# H_Bridge_Rev0_2.net
KiCad netlist of a schematic drawn in Altium Designer
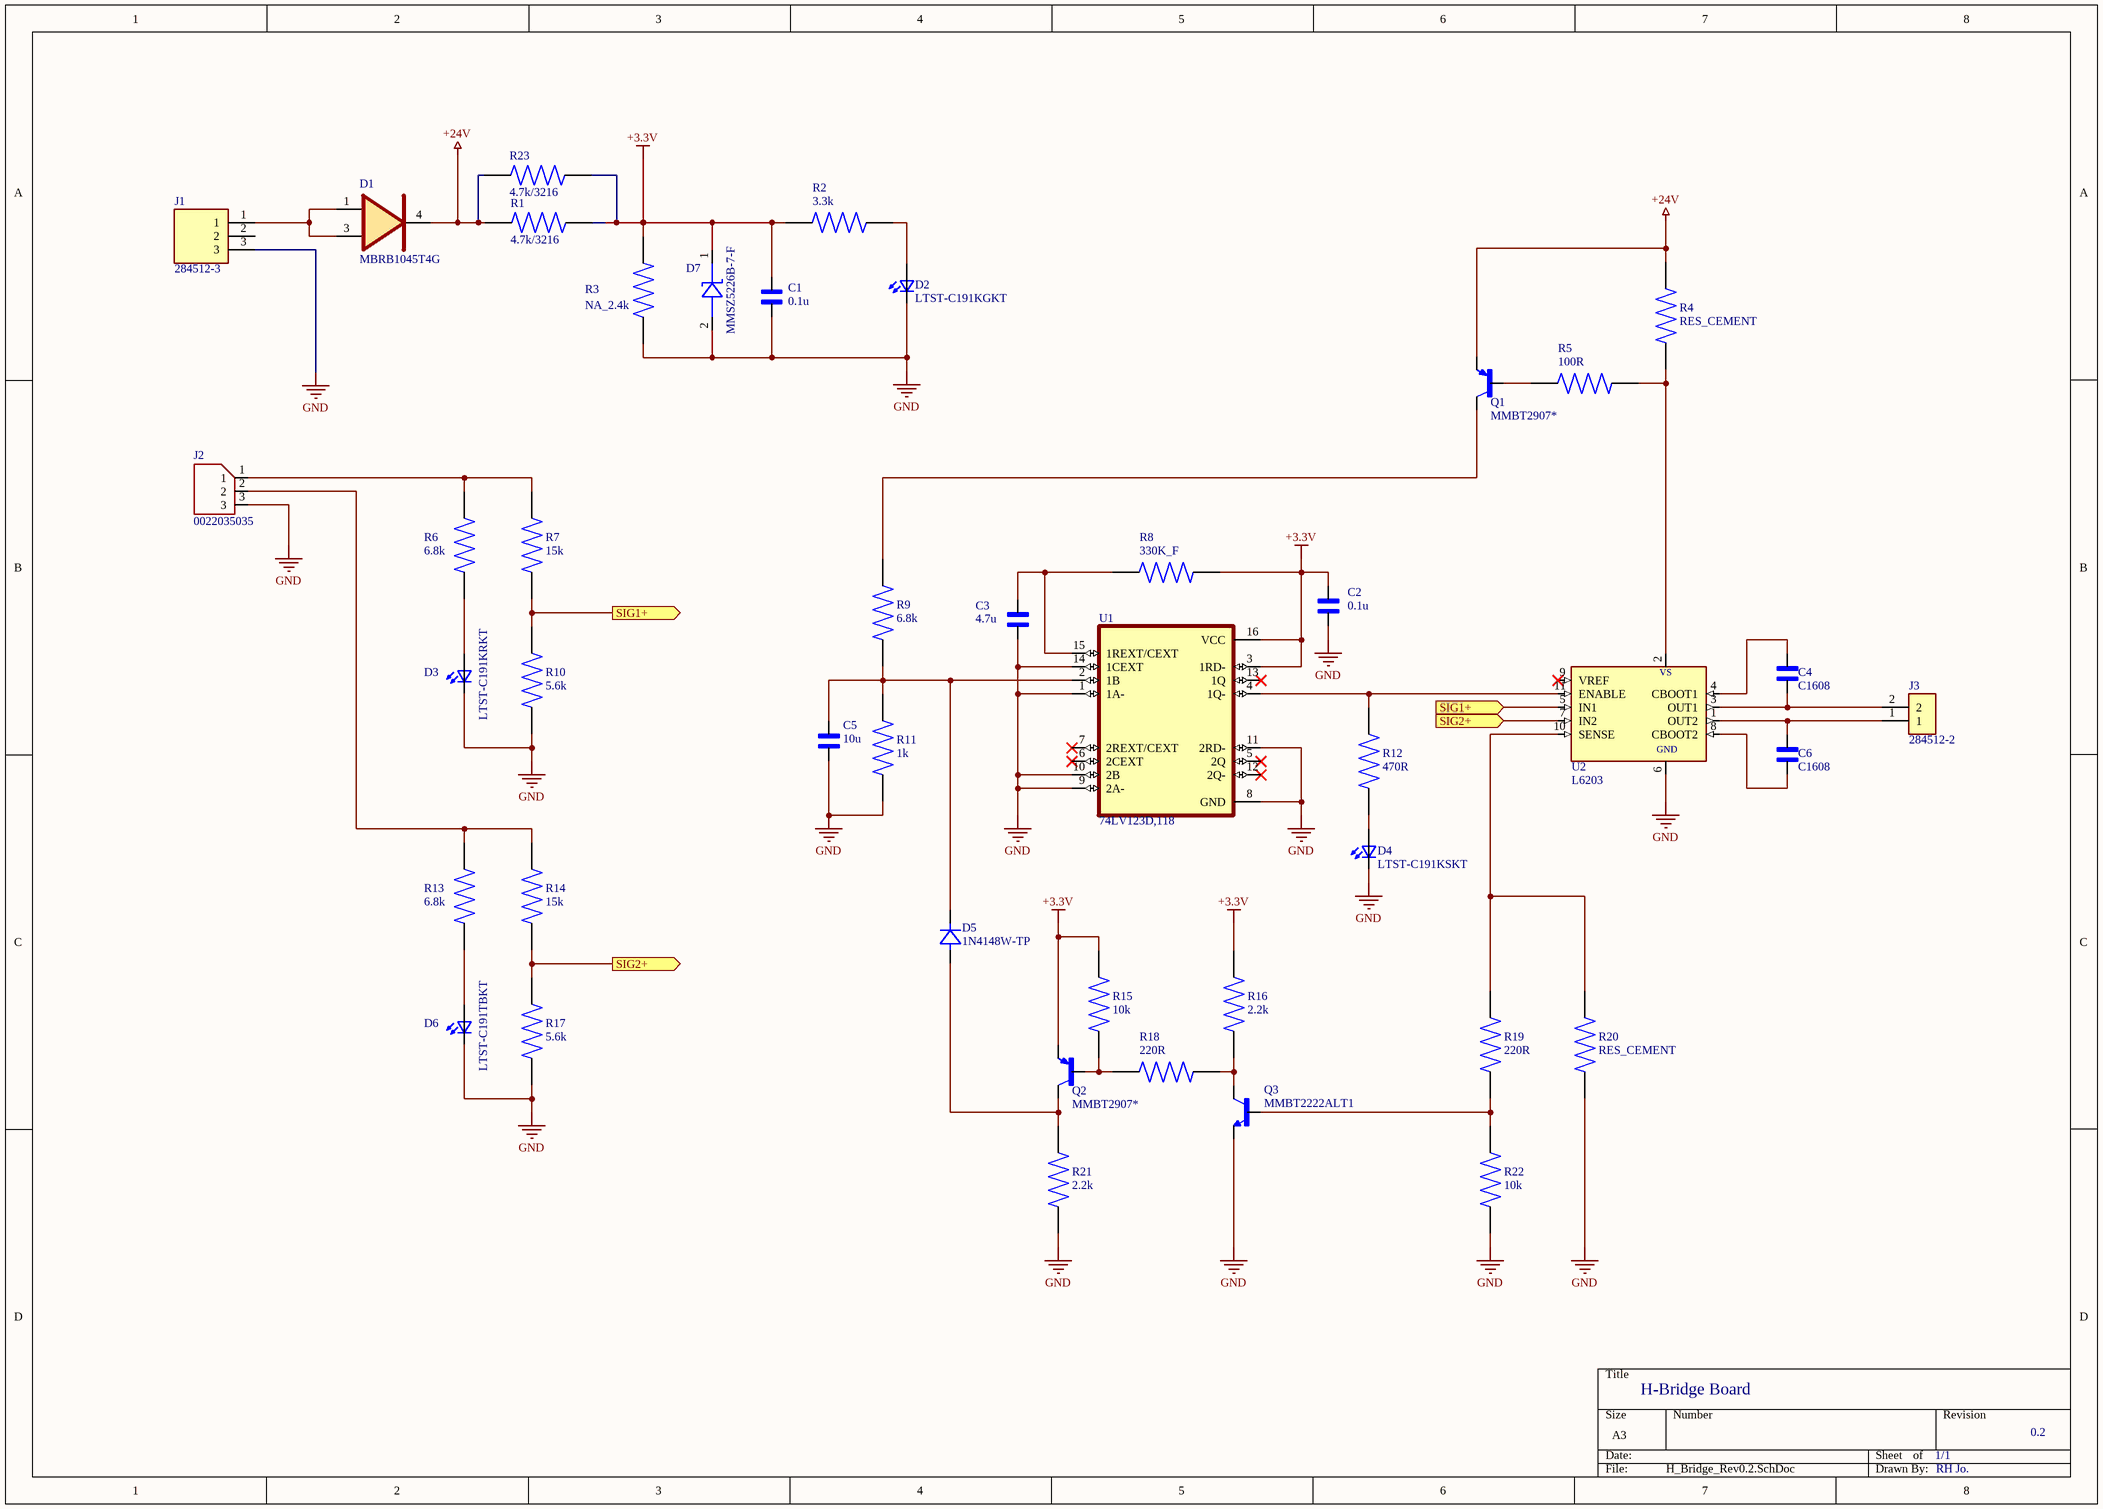
[diagram p0: H_Bridge_Rev0.2.SchDoc]

(export (version "E")
  (design (tool "Eeschema 10.0.6"))
  (components
    (comp (ref "C1")
      (value "0.1u")
      (footprint "C1608:C1608")
      (description "CAP1608")
      (libsource (lib "C1608") (part "C1608"))
    )
    (comp (ref "C2")
      (value "0.1u")
      (footprint "C1608:C1608")
      (description "CAP1608")
      (libsource (lib "C1608") (part "C1608"))
    )
    (comp (ref "C3")
      (value "4.7u")
      (footprint "C1608:C1608")
      (description "CAP1608")
      (libsource (lib "C1608") (part "C1608"))
    )
    (comp (ref "C4")
      (value "C1608")
      (footprint "C1608:C1608")
      (description "CAP1608")
      (libsource (lib "C1608") (part "C1608"))
    )
    (comp (ref "C5")
      (value "10u")
      (footprint "C1608:C1608")
      (description "CAP1608")
      (libsource (lib "C1608") (part "C1608"))
    )
    (comp (ref "C6")
      (value "C1608")
      (footprint "C1608:C1608")
      (description "CAP1608")
      (libsource (lib "C1608") (part "C1608"))
    )
    (comp (ref "D1")
      (value "MBRB1045T4G")
      (footprint "TO254P1524X483-3:TO254P1524X483-3")
      (description "Diode Schottky 45 V 10A Surface Mount DÂ²PAK")
      (fields (field (name "MF") "ON Semiconductor"))
      (libsource (lib "MBRB1045T4G") (part "MBRB1045T4G"))
    )
    (comp (ref "D2")
      (value "LTST-C191KGKT")
      (footprint "SnapEDApcb:0603")
      (description "Red 631nm LED Indication - Discrete 2V 0603 _1608 Metric_")
      (fields (field (name "MF") "Lite-On Inc.") (field (name "DIGI-KEY_PART_NUMBER") "160-1447-1-ND"))
      (libsource (lib "SnapEDAsch") (part "LTST-C191KRKT"))
    )
    (comp (ref "D3")
      (value "LTST-C191KRKT")
      (footprint "SnapEDApcb:0603")
      (description "Red 631nm LED Indication - Discrete 2V 0603 _1608 Metric_")
      (fields (field (name "MF") "Lite-On Inc.") (field (name "DIGI-KEY_PART_NUMBER") "160-1447-1-ND"))
      (libsource (lib "SnapEDAsch") (part "LTST-C191KRKT"))
    )
    (comp (ref "D4")
      (value "LTST-C191KSKT")
      (footprint "SnapEDApcb:0603")
      (description "Red 631nm LED Indication - Discrete 2V 0603 _1608 Metric_")
      (fields (field (name "MF") "Lite-On Inc.") (field (name "DIGI-KEY_PART_NUMBER") "160-1447-1-ND"))
      (libsource (lib "SnapEDAsch") (part "LTST-C191KRKT"))
    )
    (comp (ref "D5")
      (value "1N4148W-TP")
      (footprint "SnapEDApcb:SOD123")
      (description "Diode Standard 100V 150mA Surface Mount SOD-123")
      (fields (field (name "MF") "Micro Commercial"))
      (libsource (lib "SnapEDAsch") (part "1N4148W-TP"))
    )
    (comp (ref "D6")
      (value "LTST-C191TBKT")
      (footprint "SnapEDApcb:0603")
      (description "Red 631nm LED Indication - Discrete 2V 0603 _1608 Metric_")
      (fields (field (name "MF") "Lite-On Inc.") (field (name "DIGI-KEY_PART_NUMBER") "160-1447-1-ND"))
      (libsource (lib "SnapEDAsch") (part "LTST-C191KRKT"))
    )
    (comp (ref "D7")
      (value "MMSZ5226B-7-F")
      (footprint "SnapEDApcb:SOD3715X135L32X57N")
      (description "Zener Diode 3.3V 500mW Â±5% Surface Mount SOD-123")
      (fields (field (name "MF") "Diodes Inc."))
      (libsource (lib "SnapEDAsch") (part "MMSZ5226B-7-F"))
    )
    (comp (ref "J1")
      (value "284512-3")
      (footprint "SnapEDApcb:TE_284512-3")
      (description "Pluggable terminal block; socket; male; angled; 3.5mm;")
      (fields (field (name "MF") "TE Connectivity"))
      (libsource (lib "SnapEDAsch") (part "284512-3"))
    )
    (comp (ref "J2")
      (value "0022035035")
      (footprint "0022035035:MOLEX22035035")
      (description "Connector Header Through Hole 4 position 0.098 _2.50mm_")
      (fields (field (name "MP") "0022035045") (field (name "MF") "Molex, LLC"))
      (libsource (lib "0022035035") (part "0022035045"))
    )
    (comp (ref "J3")
      (value "284512-2")
      (footprint "SnapEDApcb:TE_284512-2")
      (description "Terminal Block Header, 2, 300 V, 11 A, 3.5 mm, Through Hole Right Angle, Header")
      (fields (field (name "MF") "TE Connectivity"))
      (libsource (lib "SnapEDAsch") (part "284512-2"))
    )
    (comp (ref "Q1")
      (value "MMBT2907*")
      (footprint "SnapEDApcb:SOT23-BEC")
      (description "Bipolar _BJT_ Transistor PNP 60V 600mA 200MHz 300mW Surface Mount SOT-23-3")
      (fields
        (field (name "DIGI-KEY_PART_NUMBER") "MMBT2907A-FDICT-ND")
        (field (name "MF") "ON Semiconductor")
      )
      (libsource (lib "SnapEDAsch") (part "MMBT2907*"))
    )
    (comp (ref "Q2")
      (value "MMBT2907*")
      (footprint "SnapEDApcb:SOT23-BEC")
      (description "Bipolar _BJT_ Transistor PNP 60V 600mA 200MHz 300mW Surface Mount SOT-23-3")
      (fields
        (field (name "DIGI-KEY_PART_NUMBER") "MMBT2907A-FDICT-ND")
        (field (name "MF") "ON Semiconductor")
      )
      (libsource (lib "SnapEDAsch") (part "MMBT2907*"))
    )
    (comp (ref "Q3")
      (value "MMBT2222ALT1")
      (footprint "SOT95P237X111-3N:SOT95P237X111-3N")
      (description "Bipolar (BJT) Transistor NPN 40V 600mA 300MHz 225mW Surface Mount SOT-23")
      (fields (field (name "MF") "ON Semiconductor"))
      (libsource (lib "MMBT2222ALT1") (part "MMBT2222ALT1"))
    )
    (comp (ref "R1")
      (value "4.7k/3216")
      (footprint "R3216:R3216")
      (description "Res 3216")
      (fields (field (name "TOLERANCE") "5%") (field (name "MP") "FCR1206J10R"))
      (libsource (lib "R3216") (part "R3216"))
    )
    (comp (ref "R2")
      (value "3.3k")
      (footprint "R1608:R1608")
      (description "R1608")
      (libsource (lib "R1608") (part "R1608"))
    )
    (comp (ref "R3")
      (value "NA_2.4k")
      (footprint "R1608:R1608")
      (description "R1608")
      (libsource (lib "R1608") (part "R1608"))
    )
    (comp (ref "R4")
      (value "RES_CEMENT")
      (footprint "RES_CEMENT")
      (libsource (lib "RES_CEMENT") (part "RES_CEMENT"))
    )
    (comp (ref "R5")
      (value "100R")
      (footprint "R1608:R1608")
      (description "R1608")
      (libsource (lib "R1608") (part "R1608"))
    )
    (comp (ref "R6")
      (value "6.8k")
      (footprint "R1608:R1608")
      (description "R1608")
      (libsource (lib "R1608") (part "R1608"))
    )
    (comp (ref "R7")
      (value "15k")
      (footprint "R1608:R1608")
      (description "R1608")
      (libsource (lib "R1608") (part "R1608"))
    )
    (comp (ref "R8")
      (value "330K_F")
      (footprint "R1608:R1608")
      (description "R1608")
      (libsource (lib "R1608") (part "R1608"))
    )
    (comp (ref "R9")
      (value "6.8k")
      (footprint "R1608:R1608")
      (description "R1608")
      (libsource (lib "R1608") (part "R1608"))
    )
    (comp (ref "R10")
      (value "5.6k")
      (footprint "R1608:R1608")
      (description "R1608")
      (libsource (lib "R1608") (part "R1608"))
    )
    (comp (ref "R11")
      (value "1k")
      (footprint "R1608:R1608")
      (description "R1608")
      (libsource (lib "R1608") (part "R1608"))
    )
    (comp (ref "R12")
      (value "470R")
      (footprint "R1608:R1608")
      (description "R1608")
      (libsource (lib "R1608") (part "R1608"))
    )
    (comp (ref "R13")
      (value "6.8k")
      (footprint "R1608:R1608")
      (description "R1608")
      (libsource (lib "R1608") (part "R1608"))
    )
    (comp (ref "R14")
      (value "15k")
      (footprint "R1608:R1608")
      (description "R1608")
      (libsource (lib "R1608") (part "R1608"))
    )
    (comp (ref "R15")
      (value "10k")
      (footprint "R1608:R1608")
      (description "R1608")
      (libsource (lib "R1608") (part "R1608"))
    )
    (comp (ref "R16")
      (value "2.2k")
      (footprint "R1608:R1608")
      (description "R1608")
      (libsource (lib "R1608") (part "R1608"))
    )
    (comp (ref "R17")
      (value "5.6k")
      (footprint "R1608:R1608")
      (description "R1608")
      (libsource (lib "R1608") (part "R1608"))
    )
    (comp (ref "R18")
      (value "220R")
      (footprint "R1608:R1608")
      (description "R1608")
      (libsource (lib "R1608") (part "R1608"))
    )
    (comp (ref "R19")
      (value "220R")
      (footprint "R1608:R1608")
      (description "R1608")
      (libsource (lib "R1608") (part "R1608"))
    )
    (comp (ref "R20")
      (value "RES_CEMENT")
      (footprint "RES_CEMENT")
      (libsource (lib "RES_CEMENT") (part "RES_CEMENT"))
    )
    (comp (ref "R21")
      (value "2.2k")
      (footprint "R1608:R1608")
      (description "R1608")
      (libsource (lib "R1608") (part "R1608"))
    )
    (comp (ref "R22")
      (value "10k")
      (footprint "R1608:R1608")
      (description "R1608")
      (libsource (lib "R1608") (part "R1608"))
    )
    (comp (ref "R23")
      (value "4.7k/3216")
      (footprint "R3216:R3216")
      (description "Res 3216")
      (fields (field (name "TOLERANCE") "5%") (field (name "MP") "FCR1206J10R"))
      (libsource (lib "R3216") (part "R3216"))
    )
    (comp (ref "U1")
      (value "74LV123D,118")
      (footprint "SOIC127P600X175-16N:SOIC127P600X175-16N")
      (description "Monostable Multivibrator Dual-Element -40Â°C 125Â°C Automotive 16-Pin SO T/R")
      (fields (field (name "MF") "Nexperia"))
      (libsource (lib "74LV123D,118") (part "74LV123D,118"))
    )
    (comp (ref "U2")
      (value "L6203")
      (footprint "SnapEDApcb:MULTIWATT-11")
      (description "Half Bridge _2_ Driver DC Motors, General Purpose BCDMOS 11-Multiwatt")
      (fields (field (name "MF") "STMicroelectronics"))
      (libsource (lib "SnapEDAsch") (part "L6203"))
    )
  )
  (nets
    (net (code "1") (name "+3.3V") (class "Default")
      (node (ref "C1") (pin "2") (pinfunction "2_2") (pintype "passive"))
      (node (ref "C2") (pin "2") (pinfunction "2_2") (pintype "passive"))
      (node (ref "D7") (pin "1") (pinfunction "C_1") (pintype "passive"))
      (node (ref "Q2") (pin "E") (pinfunction "E_E") (pintype "passive"))
      (node (ref "R1") (pin "2") (pinfunction "2_2") (pintype "passive"))
      (node (ref "R15") (pin "2") (pinfunction "2_2") (pintype "passive"))
      (node (ref "R16") (pin "2") (pinfunction "2_2") (pintype "passive"))
      (node (ref "R2") (pin "1") (pinfunction "1_1") (pintype "passive"))
      (node (ref "R23") (pin "2") (pinfunction "2_2") (pintype "passive"))
      (node (ref "R3") (pin "2") (pinfunction "2_2") (pintype "passive"))
      (node (ref "R8") (pin "2") (pinfunction "2_2") (pintype "passive"))
      (node (ref "U1") (pin "16") (pinfunction "VCC_16") (pintype "power_in"))
      (node (ref "U1") (pin "3") (pinfunction "1RD-_3") (pintype "bidirectional"))
    )
    (net (code "2") (name "+24V") (class "Default")
      (node (ref "D1") (pin "4") (pinfunction "OUT_4") (pintype "power_in"))
      (node (ref "Q1") (pin "E") (pinfunction "E_E") (pintype "passive"))
      (node (ref "R1") (pin "1") (pinfunction "1_1") (pintype "passive"))
      (node (ref "R23") (pin "1") (pinfunction "1_1") (pintype "passive"))
      (node (ref "R4") (pin "2") (pinfunction "2_2") (pintype "passive"))
    )
    (net (code "3") (name "/SIG1+") (class "Default")
      (node (ref "R10") (pin "2") (pinfunction "2_2") (pintype "passive"))
      (node (ref "R7") (pin "1") (pinfunction "1_1") (pintype "passive"))
      (node (ref "U2") (pin "5") (pinfunction "IN1_5") (pintype "input"))
    )
    (net (code "4") (name "/SIG2+") (class "Default")
      (node (ref "R14") (pin "1") (pinfunction "1_1") (pintype "passive"))
      (node (ref "R17") (pin "2") (pinfunction "2_2") (pintype "passive"))
      (node (ref "U2") (pin "7") (pinfunction "IN2_7") (pintype "input"))
    )
    (net (code "5") (name "GND") (class "Default")
      (node (ref "C1") (pin "1") (pinfunction "1_1") (pintype "passive"))
      (node (ref "C2") (pin "1") (pinfunction "1_1") (pintype "passive"))
      (node (ref "C3") (pin "1") (pinfunction "1_1") (pintype "passive"))
      (node (ref "C5") (pin "1") (pinfunction "1_1") (pintype "passive"))
      (node (ref "D2") (pin "1") (pinfunction "K2_1") (pintype "passive"))
      (node (ref "D3") (pin "1") (pinfunction "K2_1") (pintype "passive"))
      (node (ref "D4") (pin "1") (pinfunction "K2_1") (pintype "passive"))
      (node (ref "D6") (pin "1") (pinfunction "K2_1") (pintype "passive"))
      (node (ref "D7") (pin "2") (pinfunction "A_2") (pintype "passive"))
      (node (ref "J1") (pin "3") (pinfunction "3_3") (pintype "passive"))
      (node (ref "J2") (pin "3") (pinfunction "3_3") (pintype "passive"))
      (node (ref "Q3") (pin "2") (pinfunction "E_2") (pintype "passive"))
      (node (ref "R10") (pin "1") (pinfunction "1_1") (pintype "passive"))
      (node (ref "R11") (pin "1") (pinfunction "1_1") (pintype "passive"))
      (node (ref "R17") (pin "1") (pinfunction "1_1") (pintype "passive"))
      (node (ref "R20") (pin "1") (pinfunction "1_1") (pintype "passive"))
      (node (ref "R21") (pin "1") (pinfunction "1_1") (pintype "passive"))
      (node (ref "R22") (pin "1") (pinfunction "1_1") (pintype "passive"))
      (node (ref "R3") (pin "1") (pinfunction "1_1") (pintype "passive"))
      (node (ref "U1") (pin "1") (pinfunction "1A-_1") (pintype "bidirectional"))
      (node (ref "U1") (pin "10") (pinfunction "2B_10") (pintype "bidirectional"))
      (node (ref "U1") (pin "11") (pinfunction "2RD-_11") (pintype "bidirectional"))
      (node (ref "U1") (pin "14") (pinfunction "1CEXT_14") (pintype "bidirectional"))
      (node (ref "U1") (pin "8") (pinfunction "GND_8") (pintype "power_in"))
      (node (ref "U1") (pin "9") (pinfunction "2A-_9") (pintype "bidirectional"))
      (node (ref "U2") (pin "6") (pinfunction "GND_6") (pintype "power_in"))
    )
    (net (code "6") (name "Net-(D1-IN)") (class "Default")
      (node (ref "D1") (pin "1") (pinfunction "IN-1_1") (pintype "power_in"))
      (node (ref "D1") (pin "3") (pinfunction "IN_3") (pintype "power_in"))
      (node (ref "J1") (pin "1") (pinfunction "1_1") (pintype "passive"))
    )
    (net (code "7") (name "Net-(D2-A2)") (class "Default")
      (node (ref "D2") (pin "2") (pinfunction "A2_2") (pintype "passive"))
      (node (ref "R2") (pin "2") (pinfunction "2_2") (pintype "passive"))
    )
    (net (code "8") (name "Net-(D3-A2)") (class "Default")
      (node (ref "D3") (pin "2") (pinfunction "A2_2") (pintype "passive"))
      (node (ref "R6") (pin "1") (pinfunction "1_1") (pintype "passive"))
    )
    (net (code "9") (name "Net-(D4-A2)") (class "Default")
      (node (ref "D4") (pin "2") (pinfunction "A2_2") (pintype "passive"))
      (node (ref "R12") (pin "1") (pinfunction "1_1") (pintype "passive"))
    )
    (net (code "10") (name "Net-(D5-Pad2)") (class "Default")
      (node (ref "D5") (pin "2") (pinfunction "2_2") (pintype "passive"))
      (node (ref "Q2") (pin "C") (pinfunction "C_C") (pintype "passive"))
      (node (ref "R21") (pin "2") (pinfunction "2_2") (pintype "passive"))
    )
    (net (code "11") (name "Net-(D6-A2)") (class "Default")
      (node (ref "D6") (pin "2") (pinfunction "A2_2") (pintype "passive"))
      (node (ref "R13") (pin "1") (pinfunction "1_1") (pintype "passive"))
    )
    (net (code "12") (name "Net-(J2-Pad1)") (class "Default")
      (node (ref "J2") (pin "1") (pinfunction "1_1") (pintype "passive"))
      (node (ref "R6") (pin "2") (pinfunction "2_2") (pintype "passive"))
      (node (ref "R7") (pin "2") (pinfunction "2_2") (pintype "passive"))
    )
    (net (code "13") (name "Net-(J2-Pad2)") (class "Default")
      (node (ref "J2") (pin "2") (pinfunction "2_2") (pintype "passive"))
      (node (ref "R13") (pin "2") (pinfunction "2_2") (pintype "passive"))
      (node (ref "R14") (pin "2") (pinfunction "2_2") (pintype "passive"))
    )
    (net (code "14") (name "Net-(Q1-PadB)") (class "Default")
      (node (ref "Q1") (pin "B") (pinfunction "B_B") (pintype "passive"))
      (node (ref "R5") (pin "1") (pinfunction "1_1") (pintype "passive"))
    )
    (net (code "15") (name "Net-(Q1-PadC)") (class "Default")
      (node (ref "Q1") (pin "C") (pinfunction "C_C") (pintype "passive"))
      (node (ref "R9") (pin "2") (pinfunction "2_2") (pintype "passive"))
    )
    (net (code "16") (name "Net-(Q2-PadB)") (class "Default")
      (node (ref "Q2") (pin "B") (pinfunction "B_B") (pintype "passive"))
      (node (ref "R15") (pin "1") (pinfunction "1_1") (pintype "passive"))
      (node (ref "R18") (pin "1") (pinfunction "1_1") (pintype "passive"))
    )
    (net (code "17") (name "Net-(Q3-B)") (class "Default")
      (node (ref "Q3") (pin "1") (pinfunction "B_1") (pintype "passive"))
      (node (ref "R19") (pin "1") (pinfunction "1_1") (pintype "passive"))
      (node (ref "R22") (pin "2") (pinfunction "2_2") (pintype "passive"))
    )
    (net (code "18") (name "Net-(Q3-C)") (class "Default")
      (node (ref "Q3") (pin "3") (pinfunction "C_3") (pintype "passive"))
      (node (ref "R16") (pin "1") (pinfunction "1_1") (pintype "passive"))
      (node (ref "R18") (pin "2") (pinfunction "2_2") (pintype "passive"))
    )
    (net (code "19") (name "Net-(U1-1B)") (class "Default")
      (node (ref "C5") (pin "2") (pinfunction "2_2") (pintype "passive"))
      (node (ref "D5") (pin "1") (pinfunction "1_1") (pintype "passive"))
      (node (ref "R11") (pin "2") (pinfunction "2_2") (pintype "passive"))
      (node (ref "R9") (pin "1") (pinfunction "1_1") (pintype "passive"))
      (node (ref "U1") (pin "2") (pinfunction "1B_2") (pintype "bidirectional"))
    )
    (net (code "20") (name "Net-(U1-1Q-)") (class "Default")
      (node (ref "R12") (pin "2") (pinfunction "2_2") (pintype "passive"))
      (node (ref "U1") (pin "4") (pinfunction "1Q-_4") (pintype "bidirectional"))
      (node (ref "U2") (pin "11") (pinfunction "ENABLE_11") (pintype "input"))
    )
    (net (code "21") (name "Net-(U1-1REXT{slash}CEXT)") (class "Default")
      (node (ref "C3") (pin "2") (pinfunction "2_2") (pintype "passive"))
      (node (ref "R8") (pin "1") (pinfunction "1_1") (pintype "passive"))
      (node (ref "U1") (pin "15") (pinfunction "1REXT/CEXT_15") (pintype "bidirectional"))
    )
    (net (code "22") (name "Net-(U2-CBOOT1)") (class "Default")
      (node (ref "C4") (pin "2") (pinfunction "2_2") (pintype "passive"))
      (node (ref "U2") (pin "4") (pinfunction "CBOOT1_4") (pintype "input"))
    )
    (net (code "23") (name "Net-(U2-CBOOT2)") (class "Default")
      (node (ref "C6") (pin "1") (pinfunction "1_1") (pintype "passive"))
      (node (ref "U2") (pin "8") (pinfunction "CBOOT2_8") (pintype "input"))
    )
    (net (code "24") (name "Net-(U2-OUT1)") (class "Default")
      (node (ref "C4") (pin "1") (pinfunction "1_1") (pintype "passive"))
      (node (ref "J3") (pin "2") (pinfunction "2_2") (pintype "passive"))
      (node (ref "U2") (pin "3") (pinfunction "OUT1_3") (pintype "output"))
    )
    (net (code "25") (name "Net-(U2-OUT2)") (class "Default")
      (node (ref "C6") (pin "2") (pinfunction "2_2") (pintype "passive"))
      (node (ref "J3") (pin "1") (pinfunction "1_1") (pintype "passive"))
      (node (ref "U2") (pin "1") (pinfunction "OUT2_1") (pintype "output"))
    )
    (net (code "26") (name "Net-(U2-SENSE)") (class "Default")
      (node (ref "R19") (pin "2") (pinfunction "2_2") (pintype "passive"))
      (node (ref "R20") (pin "2") (pinfunction "2_2") (pintype "passive"))
      (node (ref "U2") (pin "10") (pinfunction "SENSE_10") (pintype "input"))
    )
    (net (code "27") (name "Net-(U2-VS)") (class "Default")
      (node (ref "R4") (pin "1") (pinfunction "1_1") (pintype "passive"))
      (node (ref "R5") (pin "2") (pinfunction "2_2") (pintype "passive"))
      (node (ref "U2") (pin "2") (pinfunction "VS_2") (pintype "power_in"))
    )
    (net (code "28") (name "unconnected-(J1-Pad2)") (class "Default")
      (node (ref "J1") (pin "2") (pinfunction "2_2") (pintype "passive"))
    )
    (net (code "29") (name "unconnected-(U1-1Q-Pad13)") (class "Default")
      (node (ref "U1") (pin "13") (pinfunction "1Q_13") (pintype "bidirectional+no_connect"))
    )
    (net (code "30") (name "unconnected-(U1-2CEXT-Pad6)") (class "Default")
      (node (ref "U1") (pin "6") (pinfunction "2CEXT_6") (pintype "bidirectional+no_connect"))
    )
    (net (code "31") (name "unconnected-(U1-2Q--Pad12)") (class "Default")
      (node (ref "U1") (pin "12") (pinfunction "2Q-_12") (pintype "bidirectional+no_connect"))
    )
    (net (code "32") (name "unconnected-(U1-2Q-Pad5)") (class "Default")
      (node (ref "U1") (pin "5") (pinfunction "2Q_5") (pintype "bidirectional+no_connect"))
    )
    (net (code "33") (name "unconnected-(U1-2REXT{slash}CEXT-Pad7)") (class "Default")
      (node (ref "U1") (pin "7") (pinfunction "2REXT/CEXT_7") (pintype "bidirectional+no_connect"))
    )
    (net (code "34") (name "unconnected-(U2-VREF-Pad9)") (class "Default")
      (node (ref "U2") (pin "9") (pinfunction "VREF_9") (pintype "input+no_connect"))
    )
  )
)
